# HPFv2.net
KiCad netlist of a schematic drawn in EAGLE
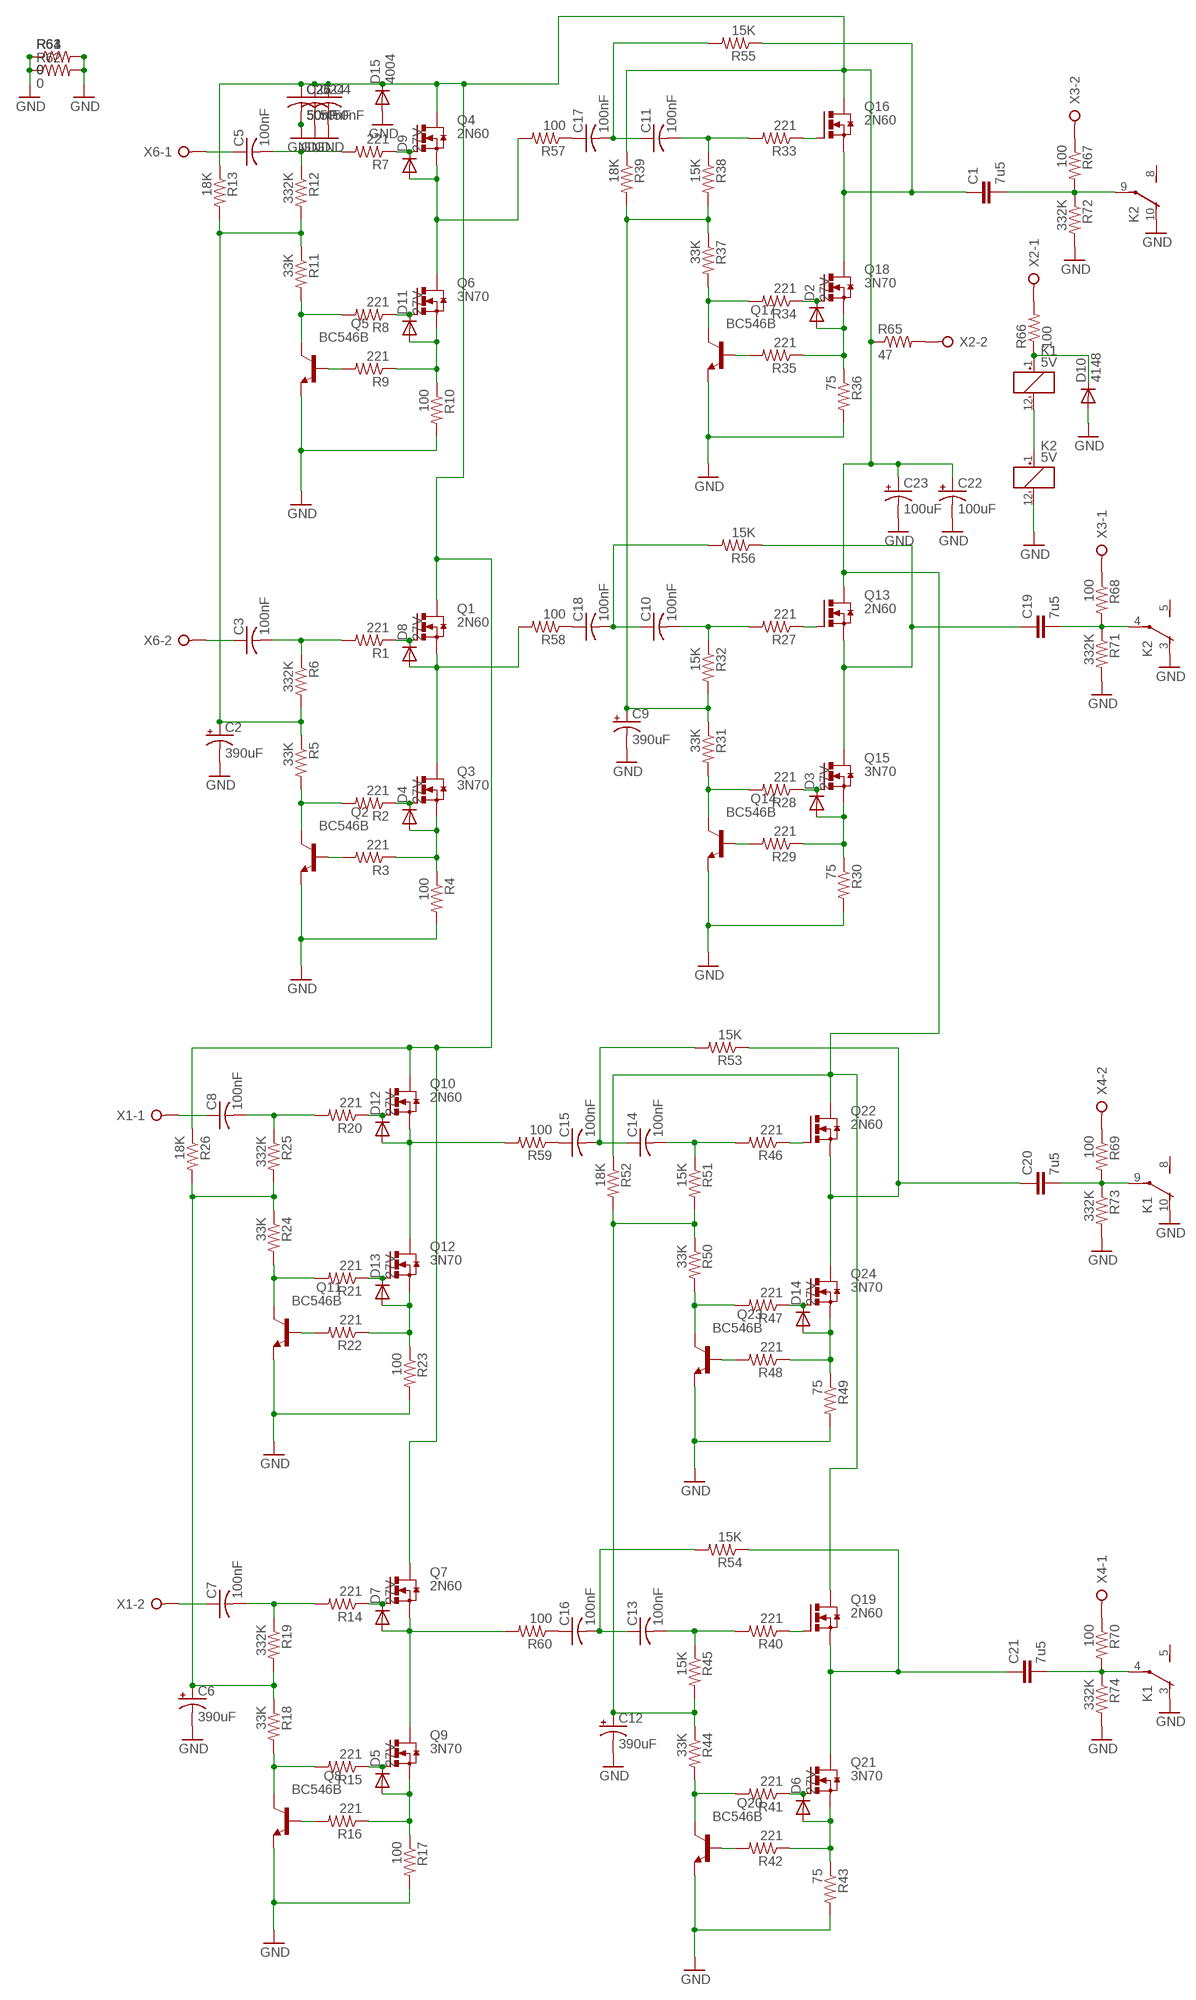
[diagram p0: schematic, sheet 1]

(export (version "E")
  (design (tool "Eeschema 10.0.6"))
  (components
    (comp (ref "C1")
      (value "7u5")
      (footprint "eagle-import:C37.5B20")
      (libsource (lib "eagle-import") (part "C37/20"))
    )
    (comp (ref "C2")
      (value "390uF")
      (footprint "eagle-import:E5-13")
      (libsource (lib "eagle-import") (part "CPOL-USE5-13"))
    )
    (comp (ref "C3")
      (value "100nF")
      (footprint "eagle-import:C050-075X075")
      (libsource (lib "eagle-import") (part "C-US050-075X075"))
    )
    (comp (ref "C4")
      (value "50nF")
      (footprint "eagle-import:C075-042X103")
      (libsource (lib "eagle-import") (part "C-US075-042X103"))
    )
    (comp (ref "C5")
      (value "100nF")
      (footprint "eagle-import:C050-075X075")
      (libsource (lib "eagle-import") (part "C-US050-075X075"))
    )
    (comp (ref "C6")
      (value "390uF")
      (footprint "eagle-import:E5-13")
      (libsource (lib "eagle-import") (part "CPOL-USE5-13"))
    )
    (comp (ref "C7")
      (value "100nF")
      (footprint "eagle-import:C050-075X075")
      (libsource (lib "eagle-import") (part "C-US050-075X075"))
    )
    (comp (ref "C8")
      (value "100nF")
      (footprint "eagle-import:C050-075X075")
      (libsource (lib "eagle-import") (part "C-US050-075X075"))
    )
    (comp (ref "C9")
      (value "390uF")
      (footprint "eagle-import:E5-13")
      (libsource (lib "eagle-import") (part "CPOL-USE5-13"))
    )
    (comp (ref "C10")
      (value "100nF")
      (footprint "eagle-import:C050-075X075")
      (libsource (lib "eagle-import") (part "C-US050-075X075"))
    )
    (comp (ref "C11")
      (value "100nF")
      (footprint "eagle-import:C050-075X075")
      (libsource (lib "eagle-import") (part "C-US050-075X075"))
    )
    (comp (ref "C12")
      (value "390uF")
      (footprint "eagle-import:E5-13")
      (libsource (lib "eagle-import") (part "CPOL-USE5-13"))
    )
    (comp (ref "C13")
      (value "100nF")
      (footprint "eagle-import:C050-075X075")
      (libsource (lib "eagle-import") (part "C-US050-075X075"))
    )
    (comp (ref "C14")
      (value "100nF")
      (footprint "eagle-import:C050-075X075")
      (libsource (lib "eagle-import") (part "C-US050-075X075"))
    )
    (comp (ref "C15")
      (value "100nF")
      (footprint "eagle-import:C050-075X075")
      (libsource (lib "eagle-import") (part "C-US050-075X075"))
    )
    (comp (ref "C16")
      (value "100nF")
      (footprint "eagle-import:C050-075X075")
      (libsource (lib "eagle-import") (part "C-US050-075X075"))
    )
    (comp (ref "C17")
      (value "100nF")
      (footprint "eagle-import:C050-075X075")
      (libsource (lib "eagle-import") (part "C-US050-075X075"))
    )
    (comp (ref "C18")
      (value "100nF")
      (footprint "eagle-import:C050-075X075")
      (libsource (lib "eagle-import") (part "C-US050-075X075"))
    )
    (comp (ref "C19")
      (value "7u5")
      (footprint "eagle-import:C37.5B20")
      (libsource (lib "eagle-import") (part "C37/20"))
    )
    (comp (ref "C20")
      (value "7u5")
      (footprint "eagle-import:C37.5B20")
      (libsource (lib "eagle-import") (part "C37/20"))
    )
    (comp (ref "C21")
      (value "7u5")
      (footprint "eagle-import:C37.5B20")
      (libsource (lib "eagle-import") (part "C37/20"))
    )
    (comp (ref "C22")
      (value "100uF")
      (footprint "eagle-import:E5-13")
      (libsource (lib "eagle-import") (part "CPOL-USE5-13"))
    )
    (comp (ref "C23")
      (value "100uF")
      (footprint "eagle-import:E5-13")
      (libsource (lib "eagle-import") (part "CPOL-USE5-13"))
    )
    (comp (ref "C24")
      (value "50nF")
      (footprint "eagle-import:C075-042X103")
      (libsource (lib "eagle-import") (part "C-US075-042X103"))
    )
    (comp (ref "C25")
      (value "50nF")
      (footprint "eagle-import:C075-042X103")
      (libsource (lib "eagle-import") (part "C-US075-042X103"))
    )
    (comp (ref "C26")
      (value "50nF")
      (footprint "eagle-import:C075-042X103")
      (libsource (lib "eagle-import") (part "C-US075-042X103"))
    )
    (comp (ref "C27")
      (value "50nF")
      (footprint "eagle-import:C075-042X103")
      (libsource (lib "eagle-import") (part "C-US075-042X103"))
    )
    (comp (ref "D2")
      (value "27V")
      (footprint "eagle-import:DO35-7")
      (libsource (lib "eagle-import") (part "1N4148DO35-7"))
    )
    (comp (ref "D3")
      (value "27V")
      (footprint "eagle-import:DO35-7")
      (libsource (lib "eagle-import") (part "1N4148DO35-7"))
    )
    (comp (ref "D4")
      (value "27V")
      (footprint "eagle-import:DO35-7")
      (libsource (lib "eagle-import") (part "1N4148DO35-7"))
    )
    (comp (ref "D5")
      (value "27V")
      (footprint "eagle-import:DO35-7")
      (libsource (lib "eagle-import") (part "1N4148DO35-7"))
    )
    (comp (ref "D6")
      (value "27V")
      (footprint "eagle-import:DO35-7")
      (libsource (lib "eagle-import") (part "1N4148DO35-7"))
    )
    (comp (ref "D7")
      (value "27V")
      (footprint "eagle-import:DO35-7")
      (libsource (lib "eagle-import") (part "1N4148DO35-7"))
    )
    (comp (ref "D8")
      (value "27V")
      (footprint "eagle-import:DO35-7")
      (libsource (lib "eagle-import") (part "1N4148DO35-7"))
    )
    (comp (ref "D9")
      (value "27V")
      (footprint "eagle-import:DO35-7")
      (libsource (lib "eagle-import") (part "1N4148DO35-7"))
    )
    (comp (ref "D10")
      (value "4148")
      (footprint "eagle-import:DO35-7")
      (libsource (lib "eagle-import") (part "1N4148DO35-7"))
    )
    (comp (ref "D11")
      (value "27V")
      (footprint "eagle-import:DO35-7")
      (libsource (lib "eagle-import") (part "1N4148DO35-7"))
    )
    (comp (ref "D12")
      (value "27V")
      (footprint "eagle-import:DO35-7")
      (libsource (lib "eagle-import") (part "1N4148DO35-7"))
    )
    (comp (ref "D13")
      (value "27V")
      (footprint "eagle-import:DO35-7")
      (libsource (lib "eagle-import") (part "1N4148DO35-7"))
    )
    (comp (ref "D14")
      (value "27V")
      (footprint "eagle-import:DO35-7")
      (libsource (lib "eagle-import") (part "1N4148DO35-7"))
    )
    (comp (ref "D15")
      (value "4004")
      (footprint "eagle-import:DO35-10")
      (libsource (lib "eagle-import") (part "1N4148DO35-10"))
    )
    (comp (ref "K1")
      (value "5V")
      (footprint "eagle-import:TX2")
      (fields (field (name "MF") "AROMAT/ MATSUSHITA") (field (name "MPN") "TX2-12V"))
      (libsource (lib "eagle-import") (part "TX2?-12V"))
    )
    (comp (ref "K2")
      (value "5V")
      (footprint "eagle-import:TX2")
      (fields (field (name "MF") "AROMAT/ MATSUSHITA") (field (name "MPN") "TX2-12V"))
      (libsource (lib "eagle-import") (part "TX2?-12V"))
    )
    (comp (ref "Q1")
      (value "2N60")
      (footprint "eagle-import:TO220BH")
      (libsource (lib "eagle-import") (part "IRFI540NPBF"))
    )
    (comp (ref "Q2")
      (value "BC546B")
      (footprint "eagle-import:TO92-EBC")
      (libsource (lib "eagle-import") (part "BC546A"))
    )
    (comp (ref "Q3")
      (value "3N70")
      (footprint "eagle-import:TO220BH")
      (libsource (lib "eagle-import") (part "IRFI540NPBF"))
    )
    (comp (ref "Q4")
      (value "2N60")
      (footprint "eagle-import:TO220BH")
      (libsource (lib "eagle-import") (part "IRFI540NPBF"))
    )
    (comp (ref "Q5")
      (value "BC546B")
      (footprint "eagle-import:TO92-EBC")
      (libsource (lib "eagle-import") (part "BC546A"))
    )
    (comp (ref "Q6")
      (value "3N70")
      (footprint "eagle-import:TO220BH")
      (libsource (lib "eagle-import") (part "IRFI540NPBF"))
    )
    (comp (ref "Q7")
      (value "2N60")
      (footprint "eagle-import:TO220BH")
      (libsource (lib "eagle-import") (part "IRFI540NPBF"))
    )
    (comp (ref "Q8")
      (value "BC546B")
      (footprint "eagle-import:TO92-EBC")
      (libsource (lib "eagle-import") (part "BC546A"))
    )
    (comp (ref "Q9")
      (value "3N70")
      (footprint "eagle-import:TO220BH")
      (libsource (lib "eagle-import") (part "IRFI540NPBF"))
    )
    (comp (ref "Q10")
      (value "2N60")
      (footprint "eagle-import:TO220BH")
      (libsource (lib "eagle-import") (part "IRFI540NPBF"))
    )
    (comp (ref "Q11")
      (value "BC546B")
      (footprint "eagle-import:TO92-EBC")
      (libsource (lib "eagle-import") (part "BC546A"))
    )
    (comp (ref "Q12")
      (value "3N70")
      (footprint "eagle-import:TO220BH")
      (libsource (lib "eagle-import") (part "IRFI540NPBF"))
    )
    (comp (ref "Q13")
      (value "2N60")
      (footprint "eagle-import:TO220BH")
      (libsource (lib "eagle-import") (part "IRFI540NPBF"))
    )
    (comp (ref "Q14")
      (value "BC546B")
      (footprint "eagle-import:TO92-EBC")
      (libsource (lib "eagle-import") (part "BC546A"))
    )
    (comp (ref "Q15")
      (value "3N70")
      (footprint "eagle-import:TO220BH")
      (libsource (lib "eagle-import") (part "IRFI540NPBF"))
    )
    (comp (ref "Q16")
      (value "2N60")
      (footprint "eagle-import:TO220BH")
      (libsource (lib "eagle-import") (part "IRFI540NPBF"))
    )
    (comp (ref "Q17")
      (value "BC546B")
      (footprint "eagle-import:TO92-EBC")
      (libsource (lib "eagle-import") (part "BC546A"))
    )
    (comp (ref "Q18")
      (value "3N70")
      (footprint "eagle-import:TO220BH")
      (libsource (lib "eagle-import") (part "IRFI540NPBF"))
    )
    (comp (ref "Q19")
      (value "2N60")
      (footprint "eagle-import:TO220BH")
      (libsource (lib "eagle-import") (part "IRFI540NPBF"))
    )
    (comp (ref "Q20")
      (value "BC546B")
      (footprint "eagle-import:TO92-EBC")
      (libsource (lib "eagle-import") (part "BC546A"))
    )
    (comp (ref "Q21")
      (value "3N70")
      (footprint "eagle-import:TO220BH")
      (libsource (lib "eagle-import") (part "IRFI540NPBF"))
    )
    (comp (ref "Q22")
      (value "2N60")
      (footprint "eagle-import:TO220BH")
      (libsource (lib "eagle-import") (part "IRFI540NPBF"))
    )
    (comp (ref "Q23")
      (value "BC546B")
      (footprint "eagle-import:TO92-EBC")
      (libsource (lib "eagle-import") (part "BC546A"))
    )
    (comp (ref "Q24")
      (value "3N70")
      (footprint "eagle-import:TO220BH")
      (libsource (lib "eagle-import") (part "IRFI540NPBF"))
    )
    (comp (ref "R1")
      (value "221")
      (footprint "eagle-import:0207_10")
      (libsource (lib "eagle-import") (part "R-US_0207/10"))
    )
    (comp (ref "R2")
      (value "221")
      (footprint "eagle-import:0207_10")
      (libsource (lib "eagle-import") (part "R-US_0207/10"))
    )
    (comp (ref "R3")
      (value "221")
      (footprint "eagle-import:0207_10")
      (libsource (lib "eagle-import") (part "R-US_0207/10"))
    )
    (comp (ref "R4")
      (value "100")
      (footprint "eagle-import:0207_10")
      (libsource (lib "eagle-import") (part "R-US_0207/10"))
    )
    (comp (ref "R5")
      (value "33K")
      (footprint "eagle-import:0207_10")
      (libsource (lib "eagle-import") (part "R-US_0207/10"))
    )
    (comp (ref "R6")
      (value "332K")
      (footprint "eagle-import:0207_10")
      (libsource (lib "eagle-import") (part "R-US_0207/10"))
    )
    (comp (ref "R7")
      (value "221")
      (footprint "eagle-import:0207_10")
      (libsource (lib "eagle-import") (part "R-US_0207/10"))
    )
    (comp (ref "R8")
      (value "221")
      (footprint "eagle-import:0207_10")
      (libsource (lib "eagle-import") (part "R-US_0207/10"))
    )
    (comp (ref "R9")
      (value "221")
      (footprint "eagle-import:0207_10")
      (libsource (lib "eagle-import") (part "R-US_0207/10"))
    )
    (comp (ref "R10")
      (value "100")
      (footprint "eagle-import:0207_10")
      (libsource (lib "eagle-import") (part "R-US_0207/10"))
    )
    (comp (ref "R11")
      (value "33K")
      (footprint "eagle-import:0207_10")
      (libsource (lib "eagle-import") (part "R-US_0207/10"))
    )
    (comp (ref "R12")
      (value "332K")
      (footprint "eagle-import:0207_10")
      (libsource (lib "eagle-import") (part "R-US_0207/10"))
    )
    (comp (ref "R13")
      (value "18K")
      (footprint "eagle-import:0207_10")
      (libsource (lib "eagle-import") (part "R-US_0207/10"))
    )
    (comp (ref "R14")
      (value "221")
      (footprint "eagle-import:0207_10")
      (libsource (lib "eagle-import") (part "R-US_0207/10"))
    )
    (comp (ref "R15")
      (value "221")
      (footprint "eagle-import:0207_10")
      (libsource (lib "eagle-import") (part "R-US_0207/10"))
    )
    (comp (ref "R16")
      (value "221")
      (footprint "eagle-import:0207_10")
      (libsource (lib "eagle-import") (part "R-US_0207/10"))
    )
    (comp (ref "R17")
      (value "100")
      (footprint "eagle-import:0207_10")
      (libsource (lib "eagle-import") (part "R-US_0207/10"))
    )
    (comp (ref "R18")
      (value "33K")
      (footprint "eagle-import:0207_10")
      (libsource (lib "eagle-import") (part "R-US_0207/10"))
    )
    (comp (ref "R19")
      (value "332K")
      (footprint "eagle-import:0207_10")
      (libsource (lib "eagle-import") (part "R-US_0207/10"))
    )
    (comp (ref "R20")
      (value "221")
      (footprint "eagle-import:0207_10")
      (libsource (lib "eagle-import") (part "R-US_0207/10"))
    )
    (comp (ref "R21")
      (value "221")
      (footprint "eagle-import:0207_10")
      (libsource (lib "eagle-import") (part "R-US_0207/10"))
    )
    (comp (ref "R22")
      (value "221")
      (footprint "eagle-import:0207_10")
      (libsource (lib "eagle-import") (part "R-US_0207/10"))
    )
    (comp (ref "R23")
      (value "100")
      (footprint "eagle-import:0207_10")
      (libsource (lib "eagle-import") (part "R-US_0207/10"))
    )
    (comp (ref "R24")
      (value "33K")
      (footprint "eagle-import:0207_10")
      (libsource (lib "eagle-import") (part "R-US_0207/10"))
    )
    (comp (ref "R25")
      (value "332K")
      (footprint "eagle-import:0207_10")
      (libsource (lib "eagle-import") (part "R-US_0207/10"))
    )
    (comp (ref "R26")
      (value "18K")
      (footprint "eagle-import:0207_10")
      (libsource (lib "eagle-import") (part "R-US_0207/10"))
    )
    (comp (ref "R27")
      (value "221")
      (footprint "eagle-import:0207_10")
      (libsource (lib "eagle-import") (part "R-US_0207/10"))
    )
    (comp (ref "R28")
      (value "221")
      (footprint "eagle-import:0207_10")
      (libsource (lib "eagle-import") (part "R-US_0207/10"))
    )
    (comp (ref "R29")
      (value "221")
      (footprint "eagle-import:0207_10")
      (libsource (lib "eagle-import") (part "R-US_0207/10"))
    )
    (comp (ref "R30")
      (value "75")
      (footprint "eagle-import:0207_10")
      (libsource (lib "eagle-import") (part "R-US_0207/10"))
    )
    (comp (ref "R31")
      (value "33K")
      (footprint "eagle-import:0207_10")
      (libsource (lib "eagle-import") (part "R-US_0207/10"))
    )
    (comp (ref "R32")
      (value "15K")
      (footprint "eagle-import:0207_10")
      (libsource (lib "eagle-import") (part "R-US_0207/10"))
    )
    (comp (ref "R33")
      (value "221")
      (footprint "eagle-import:0207_10")
      (libsource (lib "eagle-import") (part "R-US_0207/10"))
    )
    (comp (ref "R34")
      (value "221")
      (footprint "eagle-import:0207_10")
      (libsource (lib "eagle-import") (part "R-US_0207/10"))
    )
    (comp (ref "R35")
      (value "221")
      (footprint "eagle-import:0207_10")
      (libsource (lib "eagle-import") (part "R-US_0207/10"))
    )
    (comp (ref "R36")
      (value "75")
      (footprint "eagle-import:0207_10")
      (libsource (lib "eagle-import") (part "R-US_0207/10"))
    )
    (comp (ref "R37")
      (value "33K")
      (footprint "eagle-import:0207_10")
      (libsource (lib "eagle-import") (part "R-US_0207/10"))
    )
    (comp (ref "R38")
      (value "15K")
      (footprint "eagle-import:0207_10")
      (libsource (lib "eagle-import") (part "R-US_0207/10"))
    )
    (comp (ref "R39")
      (value "18K")
      (footprint "eagle-import:0207_10")
      (libsource (lib "eagle-import") (part "R-US_0207/10"))
    )
    (comp (ref "R40")
      (value "221")
      (footprint "eagle-import:0207_10")
      (libsource (lib "eagle-import") (part "R-US_0207/10"))
    )
    (comp (ref "R41")
      (value "221")
      (footprint "eagle-import:0207_10")
      (libsource (lib "eagle-import") (part "R-US_0207/10"))
    )
    (comp (ref "R42")
      (value "221")
      (footprint "eagle-import:0207_10")
      (libsource (lib "eagle-import") (part "R-US_0207/10"))
    )
    (comp (ref "R43")
      (value "75")
      (footprint "eagle-import:0207_10")
      (libsource (lib "eagle-import") (part "R-US_0207/10"))
    )
    (comp (ref "R44")
      (value "33K")
      (footprint "eagle-import:0207_10")
      (libsource (lib "eagle-import") (part "R-US_0207/10"))
    )
    (comp (ref "R45")
      (value "15K")
      (footprint "eagle-import:0207_10")
      (libsource (lib "eagle-import") (part "R-US_0207/10"))
    )
    (comp (ref "R46")
      (value "221")
      (footprint "eagle-import:0207_10")
      (libsource (lib "eagle-import") (part "R-US_0207/10"))
    )
    (comp (ref "R47")
      (value "221")
      (footprint "eagle-import:0207_10")
      (libsource (lib "eagle-import") (part "R-US_0207/10"))
    )
    (comp (ref "R48")
      (value "221")
      (footprint "eagle-import:0207_10")
      (libsource (lib "eagle-import") (part "R-US_0207/10"))
    )
    (comp (ref "R49")
      (value "75")
      (footprint "eagle-import:0207_10")
      (libsource (lib "eagle-import") (part "R-US_0207/10"))
    )
    (comp (ref "R50")
      (value "33K")
      (footprint "eagle-import:0207_10")
      (libsource (lib "eagle-import") (part "R-US_0207/10"))
    )
    (comp (ref "R51")
      (value "15K")
      (footprint "eagle-import:0207_10")
      (libsource (lib "eagle-import") (part "R-US_0207/10"))
    )
    (comp (ref "R52")
      (value "18K")
      (footprint "eagle-import:0207_10")
      (libsource (lib "eagle-import") (part "R-US_0207/10"))
    )
    (comp (ref "R53")
      (value "15K")
      (footprint "eagle-import:0207_10")
      (libsource (lib "eagle-import") (part "R-US_0207/10"))
    )
    (comp (ref "R54")
      (value "15K")
      (footprint "eagle-import:0207_10")
      (libsource (lib "eagle-import") (part "R-US_0207/10"))
    )
    (comp (ref "R55")
      (value "15K")
      (footprint "eagle-import:0207_10")
      (libsource (lib "eagle-import") (part "R-US_0207/10"))
    )
    (comp (ref "R56")
      (value "15K")
      (footprint "eagle-import:0207_10")
      (libsource (lib "eagle-import") (part "R-US_0207/10"))
    )
    (comp (ref "R57")
      (value "100")
      (footprint "eagle-import:0207_10")
      (libsource (lib "eagle-import") (part "R-US_0207/10"))
    )
    (comp (ref "R58")
      (value "100")
      (footprint "eagle-import:0207_10")
      (libsource (lib "eagle-import") (part "R-US_0207/10"))
    )
    (comp (ref "R59")
      (value "100")
      (footprint "eagle-import:0207_10")
      (libsource (lib "eagle-import") (part "R-US_0207/10"))
    )
    (comp (ref "R60")
      (value "100")
      (footprint "eagle-import:0207_10")
      (libsource (lib "eagle-import") (part "R-US_0207/10"))
    )
    (comp (ref "R61")
      (value "0")
      (footprint "eagle-import:0207_10")
      (libsource (lib "eagle-import") (part "R-US_0207/10"))
    )
    (comp (ref "R62")
      (value "0")
      (footprint "eagle-import:0204_7")
      (libsource (lib "eagle-import") (part "R-US_0204/7"))
    )
    (comp (ref "R63")
      (value "0")
      (footprint "eagle-import:0207_10")
      (libsource (lib "eagle-import") (part "R-US_0207/10"))
    )
    (comp (ref "R64")
      (value "0")
      (footprint "eagle-import:0207_10")
      (libsource (lib "eagle-import") (part "R-US_0207/10"))
    )
    (comp (ref "R65")
      (value "47")
      (footprint "eagle-import:0617_22")
      (libsource (lib "eagle-import") (part "R-US_0617/22"))
    )
    (comp (ref "R66")
      (value "100")
      (footprint "eagle-import:0309_12")
      (libsource (lib "eagle-import") (part "R-US_0309/12"))
    )
    (comp (ref "R67")
      (value "100")
      (footprint "eagle-import:0207_10")
      (libsource (lib "eagle-import") (part "R-US_0207/10"))
    )
    (comp (ref "R68")
      (value "100")
      (footprint "eagle-import:0207_10")
      (libsource (lib "eagle-import") (part "R-US_0207/10"))
    )
    (comp (ref "R69")
      (value "100")
      (footprint "eagle-import:0207_10")
      (libsource (lib "eagle-import") (part "R-US_0207/10"))
    )
    (comp (ref "R70")
      (value "100")
      (footprint "eagle-import:0207_10")
      (libsource (lib "eagle-import") (part "R-US_0207/10"))
    )
    (comp (ref "R71")
      (value "332K")
      (footprint "eagle-import:0207_10")
      (libsource (lib "eagle-import") (part "R-US_0207/10"))
    )
    (comp (ref "R72")
      (value "332K")
      (footprint "eagle-import:0207_10")
      (libsource (lib "eagle-import") (part "R-US_0207/10"))
    )
    (comp (ref "R73")
      (value "332K")
      (footprint "eagle-import:0207_10")
      (libsource (lib "eagle-import") (part "R-US_0207/10"))
    )
    (comp (ref "R74")
      (value "332K")
      (footprint "eagle-import:0207_10")
      (libsource (lib "eagle-import") (part "R-US_0207/10"))
    )
    (comp (ref "X1")
      (value "W237-02P")
      (footprint "eagle-import:W237-132")
      (fields (field (name "OC_FARNELL") "unknown") (field (name "OC_NEWARK") "unknown"))
      (libsource (lib "eagle-import") (part "W237-02P"))
    )
    (comp (ref "X2")
      (value "W237-02P")
      (footprint "eagle-import:W237-132")
      (fields (field (name "OC_FARNELL") "unknown") (field (name "OC_NEWARK") "unknown"))
      (libsource (lib "eagle-import") (part "W237-02P"))
    )
    (comp (ref "X3")
      (value "W237-02P")
      (footprint "eagle-import:W237-132")
      (fields (field (name "OC_FARNELL") "unknown") (field (name "OC_NEWARK") "unknown"))
      (libsource (lib "eagle-import") (part "W237-02P"))
    )
    (comp (ref "X4")
      (value "W237-02P")
      (footprint "eagle-import:W237-132")
      (fields (field (name "OC_FARNELL") "unknown") (field (name "OC_NEWARK") "unknown"))
      (libsource (lib "eagle-import") (part "W237-02P"))
    )
    (comp (ref "X6")
      (value "W237-02P")
      (footprint "eagle-import:W237-132")
      (fields (field (name "OC_FARNELL") "unknown") (field (name "OC_NEWARK") "unknown"))
      (libsource (lib "eagle-import") (part "W237-02P"))
    )
  )
  (nets
    (net (code "1") (name "GND") (class "Default")
      (node (ref "C12") (pin "-") (pinfunction "-_-") (pintype "passive"))
      (node (ref "C2") (pin "-") (pinfunction "-_-") (pintype "passive"))
      (node (ref "C22") (pin "-") (pinfunction "-_-") (pintype "passive"))
      (node (ref "C23") (pin "-") (pinfunction "-_-") (pintype "passive"))
      (node (ref "C24") (pin "2") (pinfunction "2_2") (pintype "passive"))
      (node (ref "C25") (pin "2") (pinfunction "2_2") (pintype "passive"))
      (node (ref "C26") (pin "2") (pinfunction "2_2") (pintype "passive"))
      (node (ref "C27") (pin "2") (pinfunction "2_2") (pintype "passive"))
      (node (ref "C4") (pin "2") (pinfunction "2_2") (pintype "passive"))
      (node (ref "C6") (pin "-") (pinfunction "-_-") (pintype "passive"))
      (node (ref "C9") (pin "-") (pinfunction "-_-") (pintype "passive"))
      (node (ref "D10") (pin "A") (pinfunction "A_A") (pintype "passive"))
      (node (ref "D15") (pin "A") (pinfunction "A_A") (pintype "passive"))
      (node (ref "K1") (pin "10") (pinfunction "O_10") (pintype "passive"))
      (node (ref "K1") (pin "3") (pinfunction "O_3") (pintype "passive"))
      (node (ref "K2") (pin "10") (pinfunction "O_10") (pintype "passive"))
      (node (ref "K2") (pin "12") (pinfunction "-_12") (pintype "passive"))
      (node (ref "K2") (pin "3") (pinfunction "O_3") (pintype "passive"))
      (node (ref "Q11") (pin "E") (pinfunction "E_E") (pintype "passive"))
      (node (ref "Q14") (pin "E") (pinfunction "E_E") (pintype "passive"))
      (node (ref "Q17") (pin "E") (pinfunction "E_E") (pintype "passive"))
      (node (ref "Q2") (pin "E") (pinfunction "E_E") (pintype "passive"))
      (node (ref "Q20") (pin "E") (pinfunction "E_E") (pintype "passive"))
      (node (ref "Q23") (pin "E") (pinfunction "E_E") (pintype "passive"))
      (node (ref "Q5") (pin "E") (pinfunction "E_E") (pintype "passive"))
      (node (ref "Q8") (pin "E") (pinfunction "E_E") (pintype "passive"))
      (node (ref "R10") (pin "2") (pinfunction "2_2") (pintype "passive"))
      (node (ref "R17") (pin "2") (pinfunction "2_2") (pintype "passive"))
      (node (ref "R23") (pin "2") (pinfunction "2_2") (pintype "passive"))
      (node (ref "R30") (pin "2") (pinfunction "2_2") (pintype "passive"))
      (node (ref "R36") (pin "2") (pinfunction "2_2") (pintype "passive"))
      (node (ref "R4") (pin "2") (pinfunction "2_2") (pintype "passive"))
      (node (ref "R43") (pin "2") (pinfunction "2_2") (pintype "passive"))
      (node (ref "R49") (pin "2") (pinfunction "2_2") (pintype "passive"))
      (node (ref "R61") (pin "1") (pinfunction "1_1") (pintype "passive"))
      (node (ref "R61") (pin "2") (pinfunction "2_2") (pintype "passive"))
      (node (ref "R62") (pin "1") (pinfunction "1_1") (pintype "passive"))
      (node (ref "R62") (pin "2") (pinfunction "2_2") (pintype "passive"))
      (node (ref "R63") (pin "1") (pinfunction "1_1") (pintype "passive"))
      (node (ref "R63") (pin "2") (pinfunction "2_2") (pintype "passive"))
      (node (ref "R64") (pin "1") (pinfunction "1_1") (pintype "passive"))
      (node (ref "R64") (pin "2") (pinfunction "2_2") (pintype "passive"))
      (node (ref "R71") (pin "2") (pinfunction "2_2") (pintype "passive"))
      (node (ref "R72") (pin "2") (pinfunction "2_2") (pintype "passive"))
      (node (ref "R73") (pin "2") (pinfunction "2_2") (pintype "passive"))
      (node (ref "R74") (pin "2") (pinfunction "2_2") (pintype "passive"))
    )
    (net (code "2") (name "Net-(C1-Pad1)") (class "Default")
      (node (ref "C1") (pin "1") (pinfunction "1_1") (pintype "passive"))
      (node (ref "Q16") (pin "S") (pinfunction "S_S") (pintype "passive"))
      (node (ref "Q18") (pin "D") (pinfunction "D_D") (pintype "passive"))
      (node (ref "R55") (pin "1") (pinfunction "1_1") (pintype "passive"))
    )
    (net (code "3") (name "Net-(C2-Pad+)") (class "Default")
      (node (ref "C2") (pin "+") (pinfunction "+_+") (pintype "passive"))
      (node (ref "R11") (pin "1") (pinfunction "1_1") (pintype "passive"))
      (node (ref "R12") (pin "2") (pinfunction "2_2") (pintype "passive"))
      (node (ref "R13") (pin "2") (pinfunction "2_2") (pintype "passive"))
      (node (ref "R5") (pin "1") (pinfunction "1_1") (pintype "passive"))
      (node (ref "R6") (pin "2") (pinfunction "2_2") (pintype "passive"))
    )
    (net (code "4") (name "Net-(C3-Pad2)") (class "Default")
      (node (ref "C3") (pin "2") (pinfunction "2_2") (pintype "passive"))
      (node (ref "R1") (pin "2") (pinfunction "2_2") (pintype "passive"))
      (node (ref "R6") (pin "1") (pinfunction "1_1") (pintype "passive"))
    )
    (net (code "5") (name "Net-(C5-Pad2)") (class "Default")
      (node (ref "C5") (pin "2") (pinfunction "2_2") (pintype "passive"))
      (node (ref "R12") (pin "1") (pinfunction "1_1") (pintype "passive"))
      (node (ref "R7") (pin "2") (pinfunction "2_2") (pintype "passive"))
    )
    (net (code "6") (name "Net-(C6-Pad+)") (class "Default")
      (node (ref "C6") (pin "+") (pinfunction "+_+") (pintype "passive"))
      (node (ref "R18") (pin "1") (pinfunction "1_1") (pintype "passive"))
      (node (ref "R19") (pin "2") (pinfunction "2_2") (pintype "passive"))
      (node (ref "R24") (pin "1") (pinfunction "1_1") (pintype "passive"))
      (node (ref "R25") (pin "2") (pinfunction "2_2") (pintype "passive"))
      (node (ref "R26") (pin "2") (pinfunction "2_2") (pintype "passive"))
    )
    (net (code "7") (name "Net-(C7-Pad2)") (class "Default")
      (node (ref "C7") (pin "2") (pinfunction "2_2") (pintype "passive"))
      (node (ref "R14") (pin "2") (pinfunction "2_2") (pintype "passive"))
      (node (ref "R19") (pin "1") (pinfunction "1_1") (pintype "passive"))
    )
    (net (code "8") (name "Net-(C8-Pad2)") (class "Default")
      (node (ref "C8") (pin "2") (pinfunction "2_2") (pintype "passive"))
      (node (ref "R20") (pin "2") (pinfunction "2_2") (pintype "passive"))
      (node (ref "R25") (pin "1") (pinfunction "1_1") (pintype "passive"))
    )
    (net (code "9") (name "Net-(C9-Pad+)") (class "Default")
      (node (ref "C9") (pin "+") (pinfunction "+_+") (pintype "passive"))
      (node (ref "R31") (pin "1") (pinfunction "1_1") (pintype "passive"))
      (node (ref "R32") (pin "2") (pinfunction "2_2") (pintype "passive"))
      (node (ref "R37") (pin "1") (pinfunction "1_1") (pintype "passive"))
      (node (ref "R38") (pin "2") (pinfunction "2_2") (pintype "passive"))
      (node (ref "R39") (pin "2") (pinfunction "2_2") (pintype "passive"))
    )
    (net (code "10") (name "Net-(C10-Pad1)") (class "Default")
      (node (ref "C10") (pin "1") (pinfunction "1_1") (pintype "passive"))
      (node (ref "C18") (pin "2") (pinfunction "2_2") (pintype "passive"))
      (node (ref "R56") (pin "2") (pinfunction "2_2") (pintype "passive"))
    )
    (net (code "11") (name "Net-(C10-Pad2)") (class "Default")
      (node (ref "C10") (pin "2") (pinfunction "2_2") (pintype "passive"))
      (node (ref "R27") (pin "2") (pinfunction "2_2") (pintype "passive"))
      (node (ref "R32") (pin "1") (pinfunction "1_1") (pintype "passive"))
    )
    (net (code "12") (name "Net-(C11-Pad1)") (class "Default")
      (node (ref "C11") (pin "1") (pinfunction "1_1") (pintype "passive"))
      (node (ref "C17") (pin "2") (pinfunction "2_2") (pintype "passive"))
      (node (ref "R55") (pin "2") (pinfunction "2_2") (pintype "passive"))
    )
    (net (code "13") (name "Net-(C11-Pad2)") (class "Default")
      (node (ref "C11") (pin "2") (pinfunction "2_2") (pintype "passive"))
      (node (ref "R33") (pin "2") (pinfunction "2_2") (pintype "passive"))
      (node (ref "R38") (pin "1") (pinfunction "1_1") (pintype "passive"))
    )
    (net (code "14") (name "Net-(C12-Pad+)") (class "Default")
      (node (ref "C12") (pin "+") (pinfunction "+_+") (pintype "passive"))
      (node (ref "R44") (pin "1") (pinfunction "1_1") (pintype "passive"))
      (node (ref "R45") (pin "2") (pinfunction "2_2") (pintype "passive"))
      (node (ref "R50") (pin "1") (pinfunction "1_1") (pintype "passive"))
      (node (ref "R51") (pin "2") (pinfunction "2_2") (pintype "passive"))
      (node (ref "R52") (pin "2") (pinfunction "2_2") (pintype "passive"))
    )
    (net (code "15") (name "Net-(C13-Pad1)") (class "Default")
      (node (ref "C13") (pin "1") (pinfunction "1_1") (pintype "passive"))
      (node (ref "C16") (pin "2") (pinfunction "2_2") (pintype "passive"))
      (node (ref "R54") (pin "2") (pinfunction "2_2") (pintype "passive"))
    )
    (net (code "16") (name "Net-(C13-Pad2)") (class "Default")
      (node (ref "C13") (pin "2") (pinfunction "2_2") (pintype "passive"))
      (node (ref "R40") (pin "2") (pinfunction "2_2") (pintype "passive"))
      (node (ref "R45") (pin "1") (pinfunction "1_1") (pintype "passive"))
    )
    (net (code "17") (name "Net-(C14-Pad1)") (class "Default")
      (node (ref "C14") (pin "1") (pinfunction "1_1") (pintype "passive"))
      (node (ref "C15") (pin "2") (pinfunction "2_2") (pintype "passive"))
      (node (ref "R53") (pin "2") (pinfunction "2_2") (pintype "passive"))
    )
    (net (code "18") (name "Net-(C14-Pad2)") (class "Default")
      (node (ref "C14") (pin "2") (pinfunction "2_2") (pintype "passive"))
      (node (ref "R46") (pin "2") (pinfunction "2_2") (pintype "passive"))
      (node (ref "R51") (pin "1") (pinfunction "1_1") (pintype "passive"))
    )
    (net (code "19") (name "Net-(C15-Pad1)") (class "Default")
      (node (ref "C15") (pin "1") (pinfunction "1_1") (pintype "passive"))
      (node (ref "R59") (pin "1") (pinfunction "1_1") (pintype "passive"))
    )
    (net (code "20") (name "Net-(C16-Pad1)") (class "Default")
      (node (ref "C16") (pin "1") (pinfunction "1_1") (pintype "passive"))
      (node (ref "R60") (pin "1") (pinfunction "1_1") (pintype "passive"))
    )
    (net (code "21") (name "Net-(C17-Pad1)") (class "Default")
      (node (ref "C17") (pin "1") (pinfunction "1_1") (pintype "passive"))
      (node (ref "R57") (pin "1") (pinfunction "1_1") (pintype "passive"))
    )
    (net (code "22") (name "Net-(C18-Pad1)") (class "Default")
      (node (ref "C18") (pin "1") (pinfunction "1_1") (pintype "passive"))
      (node (ref "R58") (pin "1") (pinfunction "1_1") (pintype "passive"))
    )
    (net (code "23") (name "Net-(C19-Pad1)") (class "Default")
      (node (ref "C19") (pin "1") (pinfunction "1_1") (pintype "passive"))
      (node (ref "Q13") (pin "S") (pinfunction "S_S") (pintype "passive"))
      (node (ref "Q15") (pin "D") (pinfunction "D_D") (pintype "passive"))
      (node (ref "R56") (pin "1") (pinfunction "1_1") (pintype "passive"))
    )
    (net (code "24") (name "Net-(C20-Pad1)") (class "Default")
      (node (ref "C20") (pin "1") (pinfunction "1_1") (pintype "passive"))
      (node (ref "Q22") (pin "S") (pinfunction "S_S") (pintype "passive"))
      (node (ref "Q24") (pin "D") (pinfunction "D_D") (pintype "passive"))
      (node (ref "R53") (pin "1") (pinfunction "1_1") (pintype "passive"))
    )
    (net (code "25") (name "Net-(C21-Pad1)") (class "Default")
      (node (ref "C21") (pin "1") (pinfunction "1_1") (pintype "passive"))
      (node (ref "Q19") (pin "S") (pinfunction "S_S") (pintype "passive"))
      (node (ref "Q21") (pin "D") (pinfunction "D_D") (pintype "passive"))
      (node (ref "R54") (pin "1") (pinfunction "1_1") (pintype "passive"))
    )
    (net (code "26") (name "Net-(C22-Pad+)") (class "Default")
      (node (ref "C22") (pin "+") (pinfunction "+_+") (pintype "passive"))
      (node (ref "C23") (pin "+") (pinfunction "+_+") (pintype "passive"))
      (node (ref "C24") (pin "1") (pinfunction "1_1") (pintype "passive"))
      (node (ref "C25") (pin "1") (pinfunction "1_1") (pintype "passive"))
      (node (ref "C26") (pin "1") (pinfunction "1_1") (pintype "passive"))
      (node (ref "C27") (pin "1") (pinfunction "1_1") (pintype "passive"))
      (node (ref "C4") (pin "1") (pinfunction "1_1") (pintype "passive"))
      (node (ref "D15") (pin "C") (pinfunction "C_C") (pintype "passive"))
      (node (ref "Q1") (pin "D") (pinfunction "D_D") (pintype "passive"))
      (node (ref "Q10") (pin "D") (pinfunction "D_D") (pintype "passive"))
      (node (ref "Q13") (pin "D") (pinfunction "D_D") (pintype "passive"))
      (node (ref "Q16") (pin "D") (pinfunction "D_D") (pintype "passive"))
      (node (ref "Q19") (pin "D") (pinfunction "D_D") (pintype "passive"))
      (node (ref "Q22") (pin "D") (pinfunction "D_D") (pintype "passive"))
      (node (ref "Q4") (pin "D") (pinfunction "D_D") (pintype "passive"))
      (node (ref "Q7") (pin "D") (pinfunction "D_D") (pintype "passive"))
      (node (ref "R13") (pin "1") (pinfunction "1_1") (pintype "passive"))
      (node (ref "R26") (pin "1") (pinfunction "1_1") (pintype "passive"))
      (node (ref "R39") (pin "1") (pinfunction "1_1") (pintype "passive"))
      (node (ref "R52") (pin "1") (pinfunction "1_1") (pintype "passive"))
      (node (ref "R65") (pin "1") (pinfunction "1_1") (pintype "passive"))
    )
    (net (code "27") (name "Net-(D2-PadA)") (class "Default")
      (node (ref "D2") (pin "A") (pinfunction "A_A") (pintype "passive"))
      (node (ref "Q18") (pin "S") (pinfunction "S_S") (pintype "passive"))
      (node (ref "R35") (pin "1") (pinfunction "1_1") (pintype "passive"))
      (node (ref "R36") (pin "1") (pinfunction "1_1") (pintype "passive"))
    )
    (net (code "28") (name "Net-(D2-PadC)") (class "Default")
      (node (ref "D2") (pin "C") (pinfunction "C_C") (pintype "passive"))
      (node (ref "Q18") (pin "G") (pinfunction "G_G") (pintype "passive"))
      (node (ref "R34") (pin "1") (pinfunction "1_1") (pintype "passive"))
    )
    (net (code "29") (name "Net-(D3-PadA)") (class "Default")
      (node (ref "D3") (pin "A") (pinfunction "A_A") (pintype "passive"))
      (node (ref "Q15") (pin "S") (pinfunction "S_S") (pintype "passive"))
      (node (ref "R29") (pin "1") (pinfunction "1_1") (pintype "passive"))
      (node (ref "R30") (pin "1") (pinfunction "1_1") (pintype "passive"))
    )
    (net (code "30") (name "Net-(D3-PadC)") (class "Default")
      (node (ref "D3") (pin "C") (pinfunction "C_C") (pintype "passive"))
      (node (ref "Q15") (pin "G") (pinfunction "G_G") (pintype "passive"))
      (node (ref "R28") (pin "1") (pinfunction "1_1") (pintype "passive"))
    )
    (net (code "31") (name "Net-(D4-PadA)") (class "Default")
      (node (ref "D4") (pin "A") (pinfunction "A_A") (pintype "passive"))
      (node (ref "Q3") (pin "S") (pinfunction "S_S") (pintype "passive"))
      (node (ref "R3") (pin "1") (pinfunction "1_1") (pintype "passive"))
      (node (ref "R4") (pin "1") (pinfunction "1_1") (pintype "passive"))
    )
    (net (code "32") (name "Net-(D4-PadC)") (class "Default")
      (node (ref "D4") (pin "C") (pinfunction "C_C") (pintype "passive"))
      (node (ref "Q3") (pin "G") (pinfunction "G_G") (pintype "passive"))
      (node (ref "R2") (pin "1") (pinfunction "1_1") (pintype "passive"))
    )
    (net (code "33") (name "Net-(D5-PadA)") (class "Default")
      (node (ref "D5") (pin "A") (pinfunction "A_A") (pintype "passive"))
      (node (ref "Q9") (pin "S") (pinfunction "S_S") (pintype "passive"))
      (node (ref "R16") (pin "1") (pinfunction "1_1") (pintype "passive"))
      (node (ref "R17") (pin "1") (pinfunction "1_1") (pintype "passive"))
    )
    (net (code "34") (name "Net-(D5-PadC)") (class "Default")
      (node (ref "D5") (pin "C") (pinfunction "C_C") (pintype "passive"))
      (node (ref "Q9") (pin "G") (pinfunction "G_G") (pintype "passive"))
      (node (ref "R15") (pin "1") (pinfunction "1_1") (pintype "passive"))
    )
    (net (code "35") (name "Net-(D6-PadA)") (class "Default")
      (node (ref "D6") (pin "A") (pinfunction "A_A") (pintype "passive"))
      (node (ref "Q21") (pin "S") (pinfunction "S_S") (pintype "passive"))
      (node (ref "R42") (pin "1") (pinfunction "1_1") (pintype "passive"))
      (node (ref "R43") (pin "1") (pinfunction "1_1") (pintype "passive"))
    )
    (net (code "36") (name "Net-(D6-PadC)") (class "Default")
      (node (ref "D6") (pin "C") (pinfunction "C_C") (pintype "passive"))
      (node (ref "Q21") (pin "G") (pinfunction "G_G") (pintype "passive"))
      (node (ref "R41") (pin "1") (pinfunction "1_1") (pintype "passive"))
    )
    (net (code "37") (name "Net-(D7-PadA)") (class "Default")
      (node (ref "D7") (pin "A") (pinfunction "A_A") (pintype "passive"))
      (node (ref "Q7") (pin "S") (pinfunction "S_S") (pintype "passive"))
      (node (ref "Q9") (pin "D") (pinfunction "D_D") (pintype "passive"))
      (node (ref "R60") (pin "2") (pinfunction "2_2") (pintype "passive"))
    )
    (net (code "38") (name "Net-(D7-PadC)") (class "Default")
      (node (ref "D7") (pin "C") (pinfunction "C_C") (pintype "passive"))
      (node (ref "Q7") (pin "G") (pinfunction "G_G") (pintype "passive"))
      (node (ref "R14") (pin "1") (pinfunction "1_1") (pintype "passive"))
    )
    (net (code "39") (name "Net-(D8-PadA)") (class "Default")
      (node (ref "D8") (pin "A") (pinfunction "A_A") (pintype "passive"))
      (node (ref "Q1") (pin "S") (pinfunction "S_S") (pintype "passive"))
      (node (ref "Q3") (pin "D") (pinfunction "D_D") (pintype "passive"))
      (node (ref "R58") (pin "2") (pinfunction "2_2") (pintype "passive"))
    )
    (net (code "40") (name "Net-(D8-PadC)") (class "Default")
      (node (ref "D8") (pin "C") (pinfunction "C_C") (pintype "passive"))
      (node (ref "Q1") (pin "G") (pinfunction "G_G") (pintype "passive"))
      (node (ref "R1") (pin "1") (pinfunction "1_1") (pintype "passive"))
    )
    (net (code "41") (name "Net-(D9-PadA)") (class "Default")
      (node (ref "D9") (pin "A") (pinfunction "A_A") (pintype "passive"))
      (node (ref "Q4") (pin "S") (pinfunction "S_S") (pintype "passive"))
      (node (ref "Q6") (pin "D") (pinfunction "D_D") (pintype "passive"))
      (node (ref "R57") (pin "2") (pinfunction "2_2") (pintype "passive"))
    )
    (net (code "42") (name "Net-(D9-PadC)") (class "Default")
      (node (ref "D9") (pin "C") (pinfunction "C_C") (pintype "passive"))
      (node (ref "Q4") (pin "G") (pinfunction "G_G") (pintype "passive"))
      (node (ref "R7") (pin "1") (pinfunction "1_1") (pintype "passive"))
    )
    (net (code "43") (name "Net-(D11-PadA)") (class "Default")
      (node (ref "D11") (pin "A") (pinfunction "A_A") (pintype "passive"))
      (node (ref "Q6") (pin "S") (pinfunction "S_S") (pintype "passive"))
      (node (ref "R10") (pin "1") (pinfunction "1_1") (pintype "passive"))
      (node (ref "R9") (pin "1") (pinfunction "1_1") (pintype "passive"))
    )
    (net (code "44") (name "Net-(D11-PadC)") (class "Default")
      (node (ref "D11") (pin "C") (pinfunction "C_C") (pintype "passive"))
      (node (ref "Q6") (pin "G") (pinfunction "G_G") (pintype "passive"))
      (node (ref "R8") (pin "1") (pinfunction "1_1") (pintype "passive"))
    )
    (net (code "45") (name "Net-(D12-PadA)") (class "Default")
      (node (ref "D12") (pin "A") (pinfunction "A_A") (pintype "passive"))
      (node (ref "Q10") (pin "S") (pinfunction "S_S") (pintype "passive"))
      (node (ref "Q12") (pin "D") (pinfunction "D_D") (pintype "passive"))
      (node (ref "R59") (pin "2") (pinfunction "2_2") (pintype "passive"))
    )
    (net (code "46") (name "Net-(D12-PadC)") (class "Default")
      (node (ref "D12") (pin "C") (pinfunction "C_C") (pintype "passive"))
      (node (ref "Q10") (pin "G") (pinfunction "G_G") (pintype "passive"))
      (node (ref "R20") (pin "1") (pinfunction "1_1") (pintype "passive"))
    )
    (net (code "47") (name "Net-(D13-PadA)") (class "Default")
      (node (ref "D13") (pin "A") (pinfunction "A_A") (pintype "passive"))
      (node (ref "Q12") (pin "S") (pinfunction "S_S") (pintype "passive"))
      (node (ref "R22") (pin "1") (pinfunction "1_1") (pintype "passive"))
      (node (ref "R23") (pin "1") (pinfunction "1_1") (pintype "passive"))
    )
    (net (code "48") (name "Net-(D13-PadC)") (class "Default")
      (node (ref "D13") (pin "C") (pinfunction "C_C") (pintype "passive"))
      (node (ref "Q12") (pin "G") (pinfunction "G_G") (pintype "passive"))
      (node (ref "R21") (pin "1") (pinfunction "1_1") (pintype "passive"))
    )
    (net (code "49") (name "Net-(D14-PadA)") (class "Default")
      (node (ref "D14") (pin "A") (pinfunction "A_A") (pintype "passive"))
      (node (ref "Q24") (pin "S") (pinfunction "S_S") (pintype "passive"))
      (node (ref "R48") (pin "1") (pinfunction "1_1") (pintype "passive"))
      (node (ref "R49") (pin "1") (pinfunction "1_1") (pintype "passive"))
    )
    (net (code "50") (name "Net-(D14-PadC)") (class "Default")
      (node (ref "D14") (pin "C") (pinfunction "C_C") (pintype "passive"))
      (node (ref "Q24") (pin "G") (pinfunction "G_G") (pintype "passive"))
      (node (ref "R47") (pin "1") (pinfunction "1_1") (pintype "passive"))
    )
    (net (code "51") (name "Net-(K1A-P)") (class "Default")
      (node (ref "C21") (pin "2") (pinfunction "2_2") (pintype "passive"))
      (node (ref "K1") (pin "4") (pinfunction "P_4") (pintype "passive"))
      (node (ref "R70") (pin "2") (pinfunction "2_2") (pintype "passive"))
      (node (ref "R74") (pin "1") (pinfunction "1_1") (pintype "passive"))
    )
    (net (code "52") (name "Net-(K1B-P)") (class "Default")
      (node (ref "C20") (pin "2") (pinfunction "2_2") (pintype "passive"))
      (node (ref "K1") (pin "9") (pinfunction "P_9") (pintype "passive"))
      (node (ref "R69") (pin "2") (pinfunction "2_2") (pintype "passive"))
      (node (ref "R73") (pin "1") (pinfunction "1_1") (pintype "passive"))
    )
    (net (code "53") (name "Net-(K1C-+)") (class "Default")
      (node (ref "D10") (pin "C") (pinfunction "C_C") (pintype "passive"))
      (node (ref "K1") (pin "1") (pinfunction "+_1") (pintype "passive"))
      (node (ref "R66") (pin "1") (pinfunction "1_1") (pintype "passive"))
    )
    (net (code "54") (name "Net-(K1C--)") (class "Default")
      (node (ref "K1") (pin "12") (pinfunction "-_12") (pintype "passive"))
      (node (ref "K2") (pin "1") (pinfunction "+_1") (pintype "passive"))
    )
    (net (code "55") (name "Net-(K2A-P)") (class "Default")
      (node (ref "C19") (pin "2") (pinfunction "2_2") (pintype "passive"))
      (node (ref "K2") (pin "4") (pinfunction "P_4") (pintype "passive"))
      (node (ref "R68") (pin "2") (pinfunction "2_2") (pintype "passive"))
      (node (ref "R71") (pin "1") (pinfunction "1_1") (pintype "passive"))
    )
    (net (code "56") (name "Net-(K2B-P)") (class "Default")
      (node (ref "C1") (pin "2") (pinfunction "2_2") (pintype "passive"))
      (node (ref "K2") (pin "9") (pinfunction "P_9") (pintype "passive"))
      (node (ref "R67") (pin "2") (pinfunction "2_2") (pintype "passive"))
      (node (ref "R72") (pin "1") (pinfunction "1_1") (pintype "passive"))
    )
    (net (code "57") (name "Net-(Q2-PadB)") (class "Default")
      (node (ref "Q2") (pin "B") (pinfunction "B_B") (pintype "passive"))
      (node (ref "R3") (pin "2") (pinfunction "2_2") (pintype "passive"))
    )
    (net (code "58") (name "Net-(Q2-PadC)") (class "Default")
      (node (ref "Q2") (pin "C") (pinfunction "C_C") (pintype "passive"))
      (node (ref "R2") (pin "2") (pinfunction "2_2") (pintype "passive"))
      (node (ref "R5") (pin "2") (pinfunction "2_2") (pintype "passive"))
    )
    (net (code "59") (name "Net-(Q5-PadB)") (class "Default")
      (node (ref "Q5") (pin "B") (pinfunction "B_B") (pintype "passive"))
      (node (ref "R9") (pin "2") (pinfunction "2_2") (pintype "passive"))
    )
    (net (code "60") (name "Net-(Q5-PadC)") (class "Default")
      (node (ref "Q5") (pin "C") (pinfunction "C_C") (pintype "passive"))
      (node (ref "R11") (pin "2") (pinfunction "2_2") (pintype "passive"))
      (node (ref "R8") (pin "2") (pinfunction "2_2") (pintype "passive"))
    )
    (net (code "61") (name "Net-(Q8-PadB)") (class "Default")
      (node (ref "Q8") (pin "B") (pinfunction "B_B") (pintype "passive"))
      (node (ref "R16") (pin "2") (pinfunction "2_2") (pintype "passive"))
    )
    (net (code "62") (name "Net-(Q8-PadC)") (class "Default")
      (node (ref "Q8") (pin "C") (pinfunction "C_C") (pintype "passive"))
      (node (ref "R15") (pin "2") (pinfunction "2_2") (pintype "passive"))
      (node (ref "R18") (pin "2") (pinfunction "2_2") (pintype "passive"))
    )
    (net (code "63") (name "Net-(Q11-PadB)") (class "Default")
      (node (ref "Q11") (pin "B") (pinfunction "B_B") (pintype "passive"))
      (node (ref "R22") (pin "2") (pinfunction "2_2") (pintype "passive"))
    )
    (net (code "64") (name "Net-(Q11-PadC)") (class "Default")
      (node (ref "Q11") (pin "C") (pinfunction "C_C") (pintype "passive"))
      (node (ref "R21") (pin "2") (pinfunction "2_2") (pintype "passive"))
      (node (ref "R24") (pin "2") (pinfunction "2_2") (pintype "passive"))
    )
    (net (code "65") (name "Net-(Q13-PadG)") (class "Default")
      (node (ref "Q13") (pin "G") (pinfunction "G_G") (pintype "passive"))
      (node (ref "R27") (pin "1") (pinfunction "1_1") (pintype "passive"))
    )
    (net (code "66") (name "Net-(Q14-PadB)") (class "Default")
      (node (ref "Q14") (pin "B") (pinfunction "B_B") (pintype "passive"))
      (node (ref "R29") (pin "2") (pinfunction "2_2") (pintype "passive"))
    )
    (net (code "67") (name "Net-(Q14-PadC)") (class "Default")
      (node (ref "Q14") (pin "C") (pinfunction "C_C") (pintype "passive"))
      (node (ref "R28") (pin "2") (pinfunction "2_2") (pintype "passive"))
      (node (ref "R31") (pin "2") (pinfunction "2_2") (pintype "passive"))
    )
    (net (code "68") (name "Net-(Q16-PadG)") (class "Default")
      (node (ref "Q16") (pin "G") (pinfunction "G_G") (pintype "passive"))
      (node (ref "R33") (pin "1") (pinfunction "1_1") (pintype "passive"))
    )
    (net (code "69") (name "Net-(Q17-PadB)") (class "Default")
      (node (ref "Q17") (pin "B") (pinfunction "B_B") (pintype "passive"))
      (node (ref "R35") (pin "2") (pinfunction "2_2") (pintype "passive"))
    )
    (net (code "70") (name "Net-(Q17-PadC)") (class "Default")
      (node (ref "Q17") (pin "C") (pinfunction "C_C") (pintype "passive"))
      (node (ref "R34") (pin "2") (pinfunction "2_2") (pintype "passive"))
      (node (ref "R37") (pin "2") (pinfunction "2_2") (pintype "passive"))
    )
    (net (code "71") (name "Net-(Q19-PadG)") (class "Default")
      (node (ref "Q19") (pin "G") (pinfunction "G_G") (pintype "passive"))
      (node (ref "R40") (pin "1") (pinfunction "1_1") (pintype "passive"))
    )
    (net (code "72") (name "Net-(Q20-PadB)") (class "Default")
      (node (ref "Q20") (pin "B") (pinfunction "B_B") (pintype "passive"))
      (node (ref "R42") (pin "2") (pinfunction "2_2") (pintype "passive"))
    )
    (net (code "73") (name "Net-(Q20-PadC)") (class "Default")
      (node (ref "Q20") (pin "C") (pinfunction "C_C") (pintype "passive"))
      (node (ref "R41") (pin "2") (pinfunction "2_2") (pintype "passive"))
      (node (ref "R44") (pin "2") (pinfunction "2_2") (pintype "passive"))
    )
    (net (code "74") (name "Net-(Q22-PadG)") (class "Default")
      (node (ref "Q22") (pin "G") (pinfunction "G_G") (pintype "passive"))
      (node (ref "R46") (pin "1") (pinfunction "1_1") (pintype "passive"))
    )
    (net (code "75") (name "Net-(Q23-PadB)") (class "Default")
      (node (ref "Q23") (pin "B") (pinfunction "B_B") (pintype "passive"))
      (node (ref "R48") (pin "2") (pinfunction "2_2") (pintype "passive"))
    )
    (net (code "76") (name "Net-(Q23-PadC)") (class "Default")
      (node (ref "Q23") (pin "C") (pinfunction "C_C") (pintype "passive"))
      (node (ref "R47") (pin "2") (pinfunction "2_2") (pintype "passive"))
      (node (ref "R50") (pin "2") (pinfunction "2_2") (pintype "passive"))
    )
    (net (code "77") (name "Net-(X1A-KL)") (class "Default")
      (node (ref "C8") (pin "1") (pinfunction "1_1") (pintype "passive"))
      (node (ref "X1") (pin "1") (pinfunction "KL_1") (pintype "passive"))
    )
    (net (code "78") (name "Net-(X1B-KL)") (class "Default")
      (node (ref "C7") (pin "1") (pinfunction "1_1") (pintype "passive"))
      (node (ref "X1") (pin "2") (pinfunction "KL_2") (pintype "passive"))
    )
    (net (code "79") (name "Net-(X2A-KL)") (class "Default")
      (node (ref "R66") (pin "2") (pinfunction "2_2") (pintype "passive"))
      (node (ref "X2") (pin "1") (pinfunction "KL_1") (pintype "passive"))
    )
    (net (code "80") (name "Net-(X2B-KL)") (class "Default")
      (node (ref "R65") (pin "2") (pinfunction "2_2") (pintype "passive"))
      (node (ref "X2") (pin "2") (pinfunction "KL_2") (pintype "passive"))
    )
    (net (code "81") (name "Net-(X3A-KL)") (class "Default")
      (node (ref "R68") (pin "1") (pinfunction "1_1") (pintype "passive"))
      (node (ref "X3") (pin "1") (pinfunction "KL_1") (pintype "passive"))
    )
    (net (code "82") (name "Net-(X3B-KL)") (class "Default")
      (node (ref "R67") (pin "1") (pinfunction "1_1") (pintype "passive"))
      (node (ref "X3") (pin "2") (pinfunction "KL_2") (pintype "passive"))
    )
    (net (code "83") (name "Net-(X4A-KL)") (class "Default")
      (node (ref "R70") (pin "1") (pinfunction "1_1") (pintype "passive"))
      (node (ref "X4") (pin "1") (pinfunction "KL_1") (pintype "passive"))
    )
    (net (code "84") (name "Net-(X4B-KL)") (class "Default")
      (node (ref "R69") (pin "1") (pinfunction "1_1") (pintype "passive"))
      (node (ref "X4") (pin "2") (pinfunction "KL_2") (pintype "passive"))
    )
    (net (code "85") (name "Net-(X6A-KL)") (class "Default")
      (node (ref "C5") (pin "1") (pinfunction "1_1") (pintype "passive"))
      (node (ref "X6") (pin "1") (pinfunction "KL_1") (pintype "passive"))
    )
    (net (code "86") (name "Net-(X6B-KL)") (class "Default")
      (node (ref "C3") (pin "1") (pinfunction "1_1") (pintype "passive"))
      (node (ref "X6") (pin "2") (pinfunction "KL_2") (pintype "passive"))
    )
    (net (code "87") (name "unconnected-(K1A-S-Pad5)") (class "Default")
      (node (ref "K1") (pin "5") (pinfunction "S_5") (pintype "passive"))
    )
    (net (code "88") (name "unconnected-(K1B-S-Pad8)") (class "Default")
      (node (ref "K1") (pin "8") (pinfunction "S_8") (pintype "passive"))
    )
    (net (code "89") (name "unconnected-(K2A-S-Pad5)") (class "Default")
      (node (ref "K2") (pin "5") (pinfunction "S_5") (pintype "passive"))
    )
    (net (code "90") (name "unconnected-(K2B-S-Pad8)") (class "Default")
      (node (ref "K2") (pin "8") (pinfunction "S_8") (pintype "passive"))
    )
  )
)
